# universky-CONNECTOR.net
KiCad netlist of a schematic drawn in Altium Designer
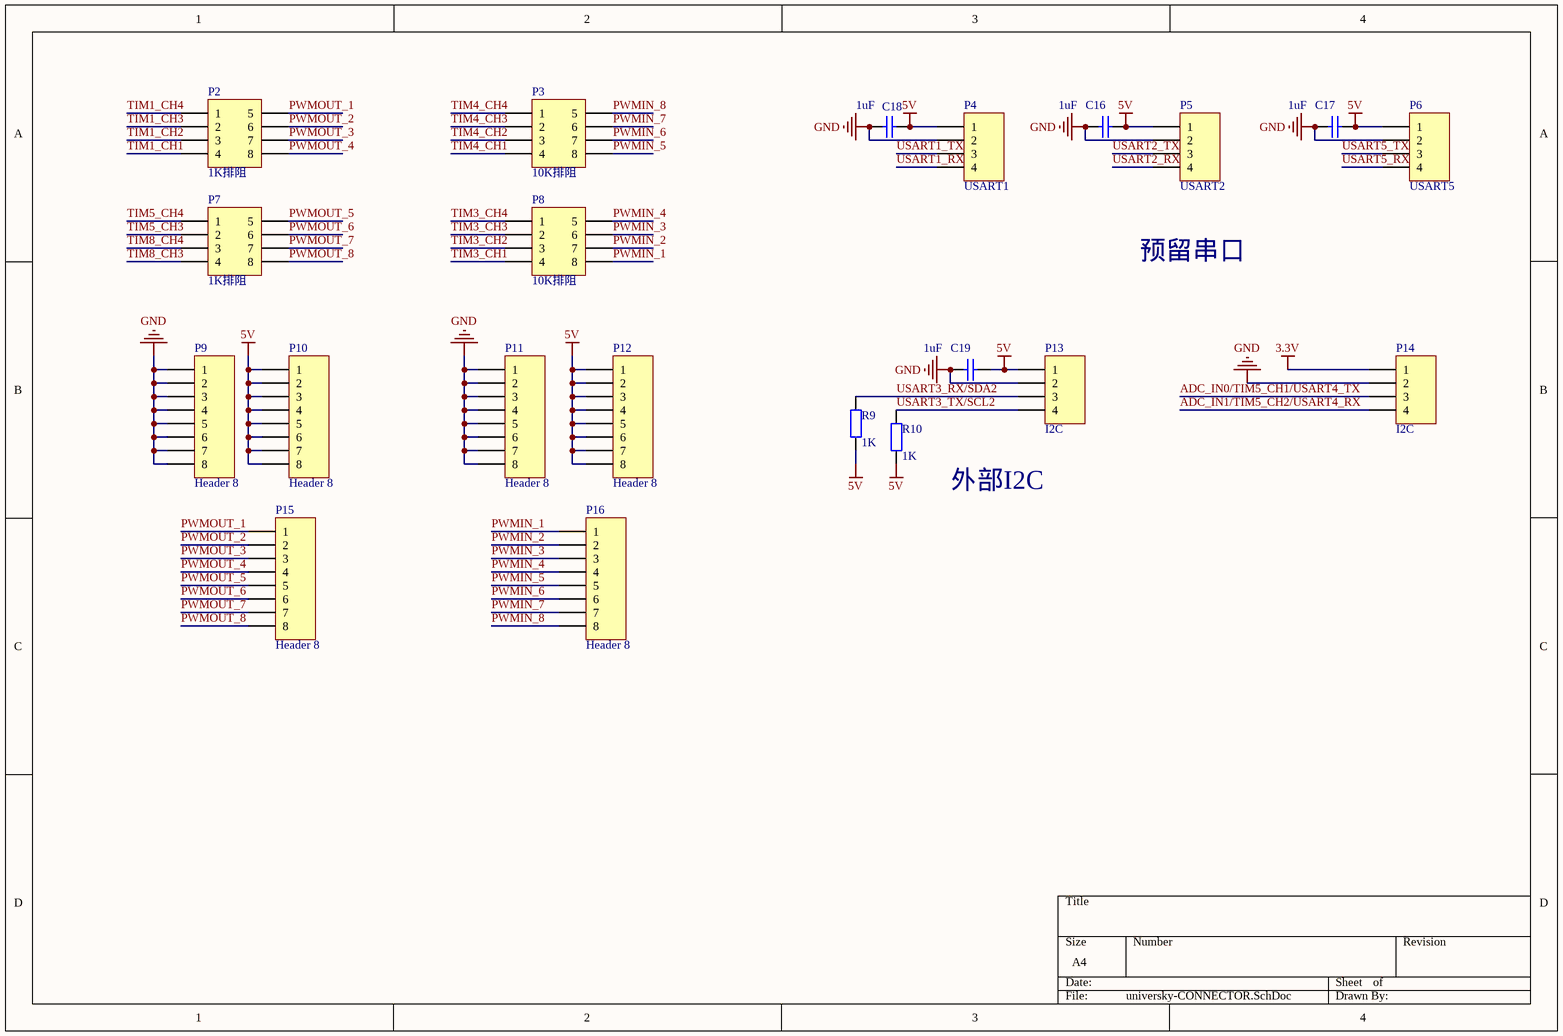
[diagram p0: universky-CONNECTOR.SchDoc]

(export (version "E")
  (design (tool "Eeschema 10.0.6"))
  (components
    (comp (ref "C16")
      (value "1uF")
      (footprint "0603_C")
      (description "Capacitor")
      (fields (field (name "Comment") "Cap") (field (name "PUBLISHER") "Altium Limited"))
      (libsource (lib "Miscellaneous Devices") (part "Cap"))
    )
    (comp (ref "C17")
      (value "1uF")
      (footprint "0603_C")
      (description "Capacitor")
      (fields (field (name "Comment") "Cap") (field (name "PUBLISHER") "Altium Limited"))
      (libsource (lib "Miscellaneous Devices") (part "Cap"))
    )
    (comp (ref "C18")
      (value "1uF")
      (footprint "0603_C")
      (description "Capacitor")
      (fields (field (name "Comment") "Cap") (field (name "PUBLISHER") "Altium Limited"))
      (libsource (lib "Miscellaneous Devices") (part "Cap"))
    )
    (comp (ref "C19")
      (value "1uF")
      (footprint "0603_C")
      (description "Capacitor")
      (fields (field (name "Comment") "Cap") (field (name "PUBLISHER") "Altium Limited"))
      (libsource (lib "Miscellaneous Devices") (part "Cap"))
    )
    (comp (ref "P2")
      (value "1K排阻")
      (footprint "HDR_R_4")
      (description "Header, 4-Pin, Dual row")
      (fields (field (name "PUBLISHER") "Altium Limited"))
      (libsource (lib "Miscellaneous Connectors") (part "Header 4X2A"))
    )
    (comp (ref "P3")
      (value "10K排阻")
      (footprint "HDR_R_4")
      (description "Header, 4-Pin, Dual row")
      (fields (field (name "PUBLISHER") "Altium Limited"))
      (libsource (lib "Miscellaneous Connectors") (part "Header 4X2A"))
    )
    (comp (ref "P4")
      (value "USART1")
      (footprint "SMD-1.25")
      (description "Header, 4-Pin")
      (fields (field (name "PUBLISHER") "Altium Limited"))
      (libsource (lib "Miscellaneous Connectors") (part "Header 4"))
    )
    (comp (ref "P5")
      (value "USART2")
      (footprint "SMD-1.25")
      (description "Header, 4-Pin")
      (fields (field (name "PUBLISHER") "Altium Limited"))
      (libsource (lib "Miscellaneous Connectors") (part "Header 4"))
    )
    (comp (ref "P6")
      (value "USART5")
      (footprint "SMD-1.25")
      (description "Header, 4-Pin")
      (fields (field (name "PUBLISHER") "Altium Limited"))
      (libsource (lib "Miscellaneous Connectors") (part "Header 4"))
    )
    (comp (ref "P7")
      (value "1K排阻")
      (footprint "HDR_R_4")
      (description "Header, 4-Pin, Dual row")
      (fields (field (name "PUBLISHER") "Altium Limited"))
      (libsource (lib "Miscellaneous Connectors") (part "Header 4X2A"))
    )
    (comp (ref "P8")
      (value "10K排阻")
      (footprint "HDR_R_4")
      (description "Header, 4-Pin, Dual row")
      (fields (field (name "PUBLISHER") "Altium Limited"))
      (libsource (lib "Miscellaneous Connectors") (part "Header 4X2A"))
    )
    (comp (ref "P9")
      (value "Header 8")
      (footprint "HDR1X8")
      (description "Header, 8-Pin")
      (fields (field (name "PUBLISHER") "Altium Limited"))
      (libsource (lib "Miscellaneous Connectors") (part "Header 8"))
    )
    (comp (ref "P10")
      (value "Header 8")
      (footprint "HDR1X8")
      (description "Header, 8-Pin")
      (fields (field (name "PUBLISHER") "Altium Limited"))
      (libsource (lib "Miscellaneous Connectors") (part "Header 8"))
    )
    (comp (ref "P11")
      (value "Header 8")
      (footprint "HDR1X8")
      (description "Header, 8-Pin")
      (fields (field (name "PUBLISHER") "Altium Limited"))
      (libsource (lib "Miscellaneous Connectors") (part "Header 8"))
    )
    (comp (ref "P12")
      (value "Header 8")
      (footprint "HDR1X8")
      (description "Header, 8-Pin")
      (fields (field (name "PUBLISHER") "Altium Limited"))
      (libsource (lib "Miscellaneous Connectors") (part "Header 8"))
    )
    (comp (ref "P13")
      (value "I2C")
      (footprint "SMD-1.25")
      (description "Header, 4-Pin")
      (fields (field (name "PUBLISHER") "Altium Limited"))
      (libsource (lib "Miscellaneous Connectors") (part "Header 4"))
    )
    (comp (ref "P14")
      (value "I2C")
      (footprint "SMD-1.25")
      (description "Header, 4-Pin")
      (fields (field (name "PUBLISHER") "Altium Limited"))
      (libsource (lib "Miscellaneous Connectors") (part "Header 4"))
    )
    (comp (ref "P15")
      (value "Header 8")
      (footprint "HDR1X8")
      (description "Header, 8-Pin")
      (fields (field (name "PUBLISHER") "Altium Limited"))
      (libsource (lib "Miscellaneous Connectors") (part "Header 8"))
    )
    (comp (ref "P16")
      (value "Header 8")
      (footprint "HDR1X8")
      (description "Header, 8-Pin")
      (fields (field (name "PUBLISHER") "Altium Limited"))
      (libsource (lib "Miscellaneous Connectors") (part "Header 8"))
    )
    (comp (ref "R9")
      (value "1K")
      (footprint "0603_R")
      (description "Resistor")
      (fields (field (name "Comment") "Res2") (field (name "PUBLISHER") "Altium Limited"))
      (libsource (lib "Miscellaneous Devices") (part "Res2"))
    )
    (comp (ref "R10")
      (value "1K")
      (footprint "0603_R")
      (description "Resistor")
      (fields (field (name "Comment") "Res2") (field (name "PUBLISHER") "Altium Limited"))
      (libsource (lib "Miscellaneous Devices") (part "Res2"))
    )
  )
  (nets
    (net (code "1") (name "/ADC_IN0{slash}TIM5_CH1{slash}USART4_TX") (class "Default")
      (node (ref "P14") (pin "3") (pinfunction "3_3") (pintype "passive"))
    )
    (net (code "2") (name "/ADC_IN1{slash}TIM5_CH2{slash}USART4_RX") (class "Default")
      (node (ref "P14") (pin "4") (pinfunction "4_4") (pintype "passive"))
    )
    (net (code "3") (name "/PWMIN_1") (class "Default")
      (node (ref "P16") (pin "1") (pinfunction "1_1") (pintype "passive"))
      (node (ref "P8") (pin "8") (pinfunction "8_8") (pintype "passive"))
    )
    (net (code "4") (name "/PWMIN_2") (class "Default")
      (node (ref "P16") (pin "2") (pinfunction "2_2") (pintype "passive"))
      (node (ref "P8") (pin "7") (pinfunction "7_7") (pintype "passive"))
    )
    (net (code "5") (name "/PWMIN_3") (class "Default")
      (node (ref "P16") (pin "3") (pinfunction "3_3") (pintype "passive"))
      (node (ref "P8") (pin "6") (pinfunction "6_6") (pintype "passive"))
    )
    (net (code "6") (name "/PWMIN_4") (class "Default")
      (node (ref "P16") (pin "4") (pinfunction "4_4") (pintype "passive"))
      (node (ref "P8") (pin "5") (pinfunction "5_5") (pintype "passive"))
    )
    (net (code "7") (name "/PWMIN_5") (class "Default")
      (node (ref "P16") (pin "5") (pinfunction "5_5") (pintype "passive"))
      (node (ref "P3") (pin "8") (pinfunction "8_8") (pintype "passive"))
    )
    (net (code "8") (name "/PWMIN_6") (class "Default")
      (node (ref "P16") (pin "6") (pinfunction "6_6") (pintype "passive"))
      (node (ref "P3") (pin "7") (pinfunction "7_7") (pintype "passive"))
    )
    (net (code "9") (name "/PWMIN_7") (class "Default")
      (node (ref "P16") (pin "7") (pinfunction "7_7") (pintype "passive"))
      (node (ref "P3") (pin "6") (pinfunction "6_6") (pintype "passive"))
    )
    (net (code "10") (name "/PWMIN_8") (class "Default")
      (node (ref "P16") (pin "8") (pinfunction "8_8") (pintype "passive"))
      (node (ref "P3") (pin "5") (pinfunction "5_5") (pintype "passive"))
    )
    (net (code "11") (name "/PWMOUT_1") (class "Default")
      (node (ref "P15") (pin "1") (pinfunction "1_1") (pintype "passive"))
      (node (ref "P2") (pin "5") (pinfunction "5_5") (pintype "passive"))
    )
    (net (code "12") (name "/PWMOUT_2") (class "Default")
      (node (ref "P15") (pin "2") (pinfunction "2_2") (pintype "passive"))
      (node (ref "P2") (pin "6") (pinfunction "6_6") (pintype "passive"))
    )
    (net (code "13") (name "/PWMOUT_3") (class "Default")
      (node (ref "P15") (pin "3") (pinfunction "3_3") (pintype "passive"))
      (node (ref "P2") (pin "7") (pinfunction "7_7") (pintype "passive"))
    )
    (net (code "14") (name "/PWMOUT_4") (class "Default")
      (node (ref "P15") (pin "4") (pinfunction "4_4") (pintype "passive"))
      (node (ref "P2") (pin "8") (pinfunction "8_8") (pintype "passive"))
    )
    (net (code "15") (name "/PWMOUT_5") (class "Default")
      (node (ref "P15") (pin "5") (pinfunction "5_5") (pintype "passive"))
      (node (ref "P7") (pin "5") (pinfunction "5_5") (pintype "passive"))
    )
    (net (code "16") (name "/PWMOUT_6") (class "Default")
      (node (ref "P15") (pin "6") (pinfunction "6_6") (pintype "passive"))
      (node (ref "P7") (pin "6") (pinfunction "6_6") (pintype "passive"))
    )
    (net (code "17") (name "/PWMOUT_7") (class "Default")
      (node (ref "P15") (pin "7") (pinfunction "7_7") (pintype "passive"))
      (node (ref "P7") (pin "7") (pinfunction "7_7") (pintype "passive"))
    )
    (net (code "18") (name "/PWMOUT_8") (class "Default")
      (node (ref "P15") (pin "8") (pinfunction "8_8") (pintype "passive"))
      (node (ref "P7") (pin "8") (pinfunction "8_8") (pintype "passive"))
    )
    (net (code "19") (name "/TIM1_CH1") (class "Default")
      (node (ref "P2") (pin "4") (pinfunction "4_4") (pintype "passive"))
    )
    (net (code "20") (name "/TIM1_CH2") (class "Default")
      (node (ref "P2") (pin "3") (pinfunction "3_3") (pintype "passive"))
    )
    (net (code "21") (name "/TIM1_CH3") (class "Default")
      (node (ref "P2") (pin "2") (pinfunction "2_2") (pintype "passive"))
    )
    (net (code "22") (name "/TIM1_CH4") (class "Default")
      (node (ref "P2") (pin "1") (pinfunction "1_1") (pintype "passive"))
    )
    (net (code "23") (name "/TIM3_CH1") (class "Default")
      (node (ref "P8") (pin "4") (pinfunction "4_4") (pintype "passive"))
    )
    (net (code "24") (name "/TIM3_CH2") (class "Default")
      (node (ref "P8") (pin "3") (pinfunction "3_3") (pintype "passive"))
    )
    (net (code "25") (name "/TIM3_CH3") (class "Default")
      (node (ref "P8") (pin "2") (pinfunction "2_2") (pintype "passive"))
    )
    (net (code "26") (name "/TIM3_CH4") (class "Default")
      (node (ref "P8") (pin "1") (pinfunction "1_1") (pintype "passive"))
    )
    (net (code "27") (name "/TIM4_CH1") (class "Default")
      (node (ref "P3") (pin "4") (pinfunction "4_4") (pintype "passive"))
    )
    (net (code "28") (name "/TIM4_CH2") (class "Default")
      (node (ref "P3") (pin "3") (pinfunction "3_3") (pintype "passive"))
    )
    (net (code "29") (name "/TIM4_CH3") (class "Default")
      (node (ref "P3") (pin "2") (pinfunction "2_2") (pintype "passive"))
    )
    (net (code "30") (name "/TIM4_CH4") (class "Default")
      (node (ref "P3") (pin "1") (pinfunction "1_1") (pintype "passive"))
    )
    (net (code "31") (name "/TIM5_CH3") (class "Default")
      (node (ref "P7") (pin "2") (pinfunction "2_2") (pintype "passive"))
    )
    (net (code "32") (name "/TIM5_CH4") (class "Default")
      (node (ref "P7") (pin "1") (pinfunction "1_1") (pintype "passive"))
    )
    (net (code "33") (name "/TIM8_CH3") (class "Default")
      (node (ref "P7") (pin "4") (pinfunction "4_4") (pintype "passive"))
    )
    (net (code "34") (name "/TIM8_CH4") (class "Default")
      (node (ref "P7") (pin "3") (pinfunction "3_3") (pintype "passive"))
    )
    (net (code "35") (name "/USART1_RX") (class "Default")
      (node (ref "P4") (pin "4") (pinfunction "4_4") (pintype "passive"))
    )
    (net (code "36") (name "/USART1_TX") (class "Default")
      (node (ref "P4") (pin "3") (pinfunction "3_3") (pintype "passive"))
    )
    (net (code "37") (name "/USART2_RX") (class "Default")
      (node (ref "P5") (pin "4") (pinfunction "4_4") (pintype "passive"))
    )
    (net (code "38") (name "/USART2_TX") (class "Default")
      (node (ref "P5") (pin "3") (pinfunction "3_3") (pintype "passive"))
    )
    (net (code "39") (name "/USART3_RX{slash}SDA2") (class "Default")
      (node (ref "P13") (pin "3") (pinfunction "3_3") (pintype "passive"))
      (node (ref "R9") (pin "2") (pinfunction "2_2") (pintype "passive"))
    )
    (net (code "40") (name "/USART3_TX{slash}SCL2") (class "Default")
      (node (ref "P13") (pin "4") (pinfunction "4_4") (pintype "passive"))
      (node (ref "R10") (pin "2") (pinfunction "2_2") (pintype "passive"))
    )
    (net (code "41") (name "/USART5_RX") (class "Default")
      (node (ref "P6") (pin "4") (pinfunction "4_4") (pintype "passive"))
    )
    (net (code "42") (name "/USART5_TX") (class "Default")
      (node (ref "P6") (pin "3") (pinfunction "3_3") (pintype "passive"))
    )
    (net (code "43") (name "3.3V") (class "Default")
      (node (ref "P14") (pin "1") (pinfunction "1_1") (pintype "passive"))
    )
    (net (code "44") (name "5V") (class "Default")
      (node (ref "C16") (pin "1") (pinfunction "1_1") (pintype "passive"))
      (node (ref "C17") (pin "1") (pinfunction "1_1") (pintype "passive"))
      (node (ref "C18") (pin "1") (pinfunction "1_1") (pintype "passive"))
      (node (ref "C19") (pin "1") (pinfunction "1_1") (pintype "passive"))
      (node (ref "P10") (pin "1") (pinfunction "1_1") (pintype "passive"))
      (node (ref "P10") (pin "2") (pinfunction "2_2") (pintype "passive"))
      (node (ref "P10") (pin "3") (pinfunction "3_3") (pintype "passive"))
      (node (ref "P10") (pin "4") (pinfunction "4_4") (pintype "passive"))
      (node (ref "P10") (pin "5") (pinfunction "5_5") (pintype "passive"))
      (node (ref "P10") (pin "6") (pinfunction "6_6") (pintype "passive"))
      (node (ref "P10") (pin "7") (pinfunction "7_7") (pintype "passive"))
      (node (ref "P10") (pin "8") (pinfunction "8_8") (pintype "passive"))
      (node (ref "P12") (pin "1") (pinfunction "1_1") (pintype "passive"))
      (node (ref "P12") (pin "2") (pinfunction "2_2") (pintype "passive"))
      (node (ref "P12") (pin "3") (pinfunction "3_3") (pintype "passive"))
      (node (ref "P12") (pin "4") (pinfunction "4_4") (pintype "passive"))
      (node (ref "P12") (pin "5") (pinfunction "5_5") (pintype "passive"))
      (node (ref "P12") (pin "6") (pinfunction "6_6") (pintype "passive"))
      (node (ref "P12") (pin "7") (pinfunction "7_7") (pintype "passive"))
      (node (ref "P12") (pin "8") (pinfunction "8_8") (pintype "passive"))
      (node (ref "P13") (pin "1") (pinfunction "1_1") (pintype "passive"))
      (node (ref "P4") (pin "1") (pinfunction "1_1") (pintype "passive"))
      (node (ref "P5") (pin "1") (pinfunction "1_1") (pintype "passive"))
      (node (ref "P6") (pin "1") (pinfunction "1_1") (pintype "passive"))
      (node (ref "R10") (pin "1") (pinfunction "1_1") (pintype "passive"))
      (node (ref "R9") (pin "1") (pinfunction "1_1") (pintype "passive"))
    )
    (net (code "45") (name "GND") (class "Default")
      (node (ref "C16") (pin "2") (pinfunction "2_2") (pintype "passive"))
      (node (ref "C17") (pin "2") (pinfunction "2_2") (pintype "passive"))
      (node (ref "C18") (pin "2") (pinfunction "2_2") (pintype "passive"))
      (node (ref "C19") (pin "2") (pinfunction "2_2") (pintype "passive"))
      (node (ref "P11") (pin "1") (pinfunction "1_1") (pintype "passive"))
      (node (ref "P11") (pin "2") (pinfunction "2_2") (pintype "passive"))
      (node (ref "P11") (pin "3") (pinfunction "3_3") (pintype "passive"))
      (node (ref "P11") (pin "4") (pinfunction "4_4") (pintype "passive"))
      (node (ref "P11") (pin "5") (pinfunction "5_5") (pintype "passive"))
      (node (ref "P11") (pin "6") (pinfunction "6_6") (pintype "passive"))
      (node (ref "P11") (pin "7") (pinfunction "7_7") (pintype "passive"))
      (node (ref "P11") (pin "8") (pinfunction "8_8") (pintype "passive"))
      (node (ref "P13") (pin "2") (pinfunction "2_2") (pintype "passive"))
      (node (ref "P14") (pin "2") (pinfunction "2_2") (pintype "passive"))
      (node (ref "P4") (pin "2") (pinfunction "2_2") (pintype "passive"))
      (node (ref "P5") (pin "2") (pinfunction "2_2") (pintype "passive"))
      (node (ref "P6") (pin "2") (pinfunction "2_2") (pintype "passive"))
      (node (ref "P9") (pin "1") (pinfunction "1_1") (pintype "passive"))
      (node (ref "P9") (pin "2") (pinfunction "2_2") (pintype "passive"))
      (node (ref "P9") (pin "3") (pinfunction "3_3") (pintype "passive"))
      (node (ref "P9") (pin "4") (pinfunction "4_4") (pintype "passive"))
      (node (ref "P9") (pin "5") (pinfunction "5_5") (pintype "passive"))
      (node (ref "P9") (pin "6") (pinfunction "6_6") (pintype "passive"))
      (node (ref "P9") (pin "7") (pinfunction "7_7") (pintype "passive"))
      (node (ref "P9") (pin "8") (pinfunction "8_8") (pintype "passive"))
    )
  )
)
